# Rele-TTL.net
KiCad netlist of a schematic drawn in EAGLE
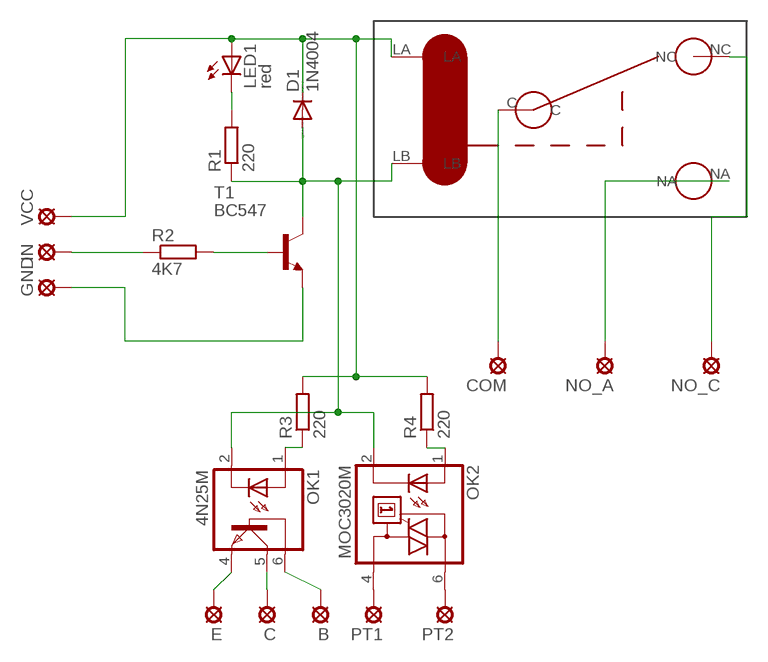
[diagram p0: schematic, sheet 1]

(export (version "E")
  (design (tool "Eeschema 10.0.6"))
  (components
    (comp (ref "B")
      (value "LSP10")
      (footprint "eagle-import:LSP10")
      (libsource (lib "eagle-import") (part "LSP10"))
    )
    (comp (ref "C")
      (value "LSP10")
      (footprint "eagle-import:LSP10")
      (libsource (lib "eagle-import") (part "LSP10"))
    )
    (comp (ref "COM")
      (value "LSP10")
      (footprint "eagle-import:LSP10")
      (libsource (lib "eagle-import") (part "LSP10"))
    )
    (comp (ref "D1")
      (value "1N4004")
      (footprint "eagle-import:DO41-10")
      (libsource (lib "eagle-import") (part "1N4004"))
    )
    (comp (ref "E")
      (value "LSP10")
      (footprint "eagle-import:LSP10")
      (libsource (lib "eagle-import") (part "LSP10"))
    )
    (comp (ref "GND")
      (value "LSP10")
      (footprint "eagle-import:LSP10")
      (libsource (lib "eagle-import") (part "LSP10"))
    )
    (comp (ref "IN")
      (value "LSP10")
      (footprint "eagle-import:LSP10")
      (libsource (lib "eagle-import") (part "LSP10"))
    )
    (comp (ref "LED1")
      (value "red")
      (footprint "eagle-import:LED5MM")
      (libsource (lib "eagle-import") (part "LED5MM"))
    )
    (comp (ref "NO_A")
      (value "LSP10")
      (footprint "eagle-import:LSP10")
      (libsource (lib "eagle-import") (part "LSP10"))
    )
    (comp (ref "NO_C")
      (value "LSP10")
      (footprint "eagle-import:LSP10")
      (libsource (lib "eagle-import") (part "LSP10"))
    )
    (comp (ref "OK1")
      (value "4N25M")
      (footprint "eagle-import:DIL06")
      (fields (field (name "MPN") "4N25-M"))
      (libsource (lib "eagle-import") (part "4N?M25"))
    )
    (comp (ref "OK2")
      (value "MOC3020M")
      (footprint "eagle-import:DIL06")
      (fields (field (name "MF") "FAIRCHILD SEMICONDUCTOR") (field (name "MPN") "MOC3020-M"))
      (libsource (lib "eagle-import") (part "MOC30M20"))
    )
    (comp (ref "PT1")
      (value "LSP10")
      (footprint "eagle-import:LSP10")
      (libsource (lib "eagle-import") (part "LSP10"))
    )
    (comp (ref "PT2")
      (value "LSP10")
      (footprint "eagle-import:LSP10")
      (libsource (lib "eagle-import") (part "LSP10"))
    )
    (comp (ref "R1")
      (value "220")
      (footprint "eagle-import:0207_10")
      (libsource (lib "eagle-import") (part "R-EU_0207/10"))
    )
    (comp (ref "R2")
      (value "4K7")
      (footprint "eagle-import:0207_10")
      (libsource (lib "eagle-import") (part "R-EU_0207/10"))
    )
    (comp (ref "R3")
      (value "220")
      (footprint "eagle-import:0207_10")
      (libsource (lib "eagle-import") (part "R-EU_0207/10"))
    )
    (comp (ref "R4")
      (value "220")
      (footprint "eagle-import:0207_10")
      (libsource (lib "eagle-import") (part "R-EU_0207/10"))
    )
    (comp (ref "RL1")
      (value "RELE")
      (footprint "eagle-import:RELE_1")
      (libsource (lib "eagle-import") (part "RELE"))
    )
    (comp (ref "T1")
      (value "BC547")
      (footprint "eagle-import:TO92")
      (libsource (lib "eagle-import") (part "BC547"))
    )
    (comp (ref "VCC")
      (value "LSP10")
      (footprint "eagle-import:LSP10")
      (libsource (lib "eagle-import") (part "LSP10"))
    )
  )
  (nets
    (net (code "1") (name "Net-(COM-PadMP)") (class "Default")
      (node (ref "COM") (pin "MP") (pinfunction "MP_MP") (pintype "passive"))
      (node (ref "RL1") (pin "C") (pinfunction "C_C") (pintype "bidirectional"))
    )
    (net (code "2") (name "Net-(D1-PadC)") (class "Default")
      (node (ref "D1") (pin "C") (pinfunction "C_C") (pintype "passive"))
      (node (ref "LED1") (pin "A") (pinfunction "A_A") (pintype "passive"))
      (node (ref "R3") (pin "2") (pinfunction "2_2") (pintype "passive"))
      (node (ref "R4") (pin "2") (pinfunction "2_2") (pintype "passive"))
      (node (ref "RL1") (pin "LA") (pinfunction "LA_LA") (pintype "bidirectional"))
      (node (ref "VCC") (pin "MP") (pinfunction "MP_MP") (pintype "passive"))
    )
    (net (code "3") (name "Net-(IN-PadMP)") (class "Default")
      (node (ref "IN") (pin "MP") (pinfunction "MP_MP") (pintype "passive"))
      (node (ref "R2") (pin "1") (pinfunction "1_1") (pintype "passive"))
    )
    (net (code "4") (name "Net-(LED1-C)") (class "Default")
      (node (ref "LED1") (pin "K") (pinfunction "C_K") (pintype "passive"))
      (node (ref "R1") (pin "2") (pinfunction "2_2") (pintype "passive"))
    )
    (net (code "5") (name "Net-(NO_A-PadMP)") (class "Default")
      (node (ref "NO_A") (pin "MP") (pinfunction "MP_MP") (pintype "passive"))
      (node (ref "RL1") (pin "NA") (pinfunction "NA_NA") (pintype "bidirectional"))
    )
    (net (code "6") (name "Net-(NO_C-PadMP)") (class "Default")
      (node (ref "NO_C") (pin "MP") (pinfunction "MP_MP") (pintype "passive"))
      (node (ref "RL1") (pin "NC") (pinfunction "NC_NC") (pintype "bidirectional"))
    )
    (net (code "7") (name "Net-(OK1-A)") (class "Default")
      (node (ref "OK1") (pin "1") (pinfunction "A_1") (pintype "passive"))
      (node (ref "R3") (pin "1") (pinfunction "1_1") (pintype "passive"))
    )
    (net (code "8") (name "Net-(OK1-BAS)") (class "Default")
      (node (ref "B") (pin "MP") (pinfunction "MP_MP") (pintype "passive"))
      (node (ref "OK1") (pin "6") (pinfunction "BAS_6") (pintype "passive"))
    )
    (net (code "9") (name "Net-(OK1-C)") (class "Default")
      (node (ref "D1") (pin "A") (pinfunction "A_A") (pintype "passive"))
      (node (ref "OK1") (pin "2") (pinfunction "C_2") (pintype "passive"))
      (node (ref "OK2") (pin "2") (pinfunction "C_2") (pintype "passive"))
      (node (ref "R1") (pin "1") (pinfunction "1_1") (pintype "passive"))
      (node (ref "RL1") (pin "LB") (pinfunction "LB_LB") (pintype "bidirectional"))
      (node (ref "T1") (pin "3") (pinfunction "C_3") (pintype "passive"))
    )
    (net (code "10") (name "Net-(OK1-COL)") (class "Default")
      (node (ref "C") (pin "MP") (pinfunction "MP_MP") (pintype "passive"))
      (node (ref "OK1") (pin "5") (pinfunction "COL_5") (pintype "passive"))
    )
    (net (code "11") (name "Net-(OK1-EMI)") (class "Default")
      (node (ref "E") (pin "MP") (pinfunction "MP_MP") (pintype "passive"))
      (node (ref "OK1") (pin "4") (pinfunction "EMI_4") (pintype "passive"))
    )
    (net (code "12") (name "Net-(OK2-A)") (class "Default")
      (node (ref "OK2") (pin "1") (pinfunction "A_1") (pintype "passive"))
      (node (ref "R4") (pin "1") (pinfunction "1_1") (pintype "passive"))
    )
    (net (code "13") (name "Net-(OK2-A1)") (class "Default")
      (node (ref "OK2") (pin "4") (pinfunction "A1_4") (pintype "passive"))
      (node (ref "PT1") (pin "MP") (pinfunction "MP_MP") (pintype "passive"))
    )
    (net (code "14") (name "Net-(OK2-A2)") (class "Default")
      (node (ref "OK2") (pin "6") (pinfunction "A2_6") (pintype "passive"))
      (node (ref "PT2") (pin "MP") (pinfunction "MP_MP") (pintype "passive"))
    )
    (net (code "15") (name "Net-(T1-B)") (class "Default")
      (node (ref "R2") (pin "2") (pinfunction "2_2") (pintype "passive"))
      (node (ref "T1") (pin "2") (pinfunction "B_2") (pintype "passive"))
    )
    (net (code "16") (name "Net-(T1-E)") (class "Default")
      (node (ref "GND") (pin "MP") (pinfunction "MP_MP") (pintype "passive"))
      (node (ref "T1") (pin "1") (pinfunction "E_1") (pintype "passive"))
    )
  )
)
